# BatchE.net
KiCad netlist of a schematic drawn in EAGLE
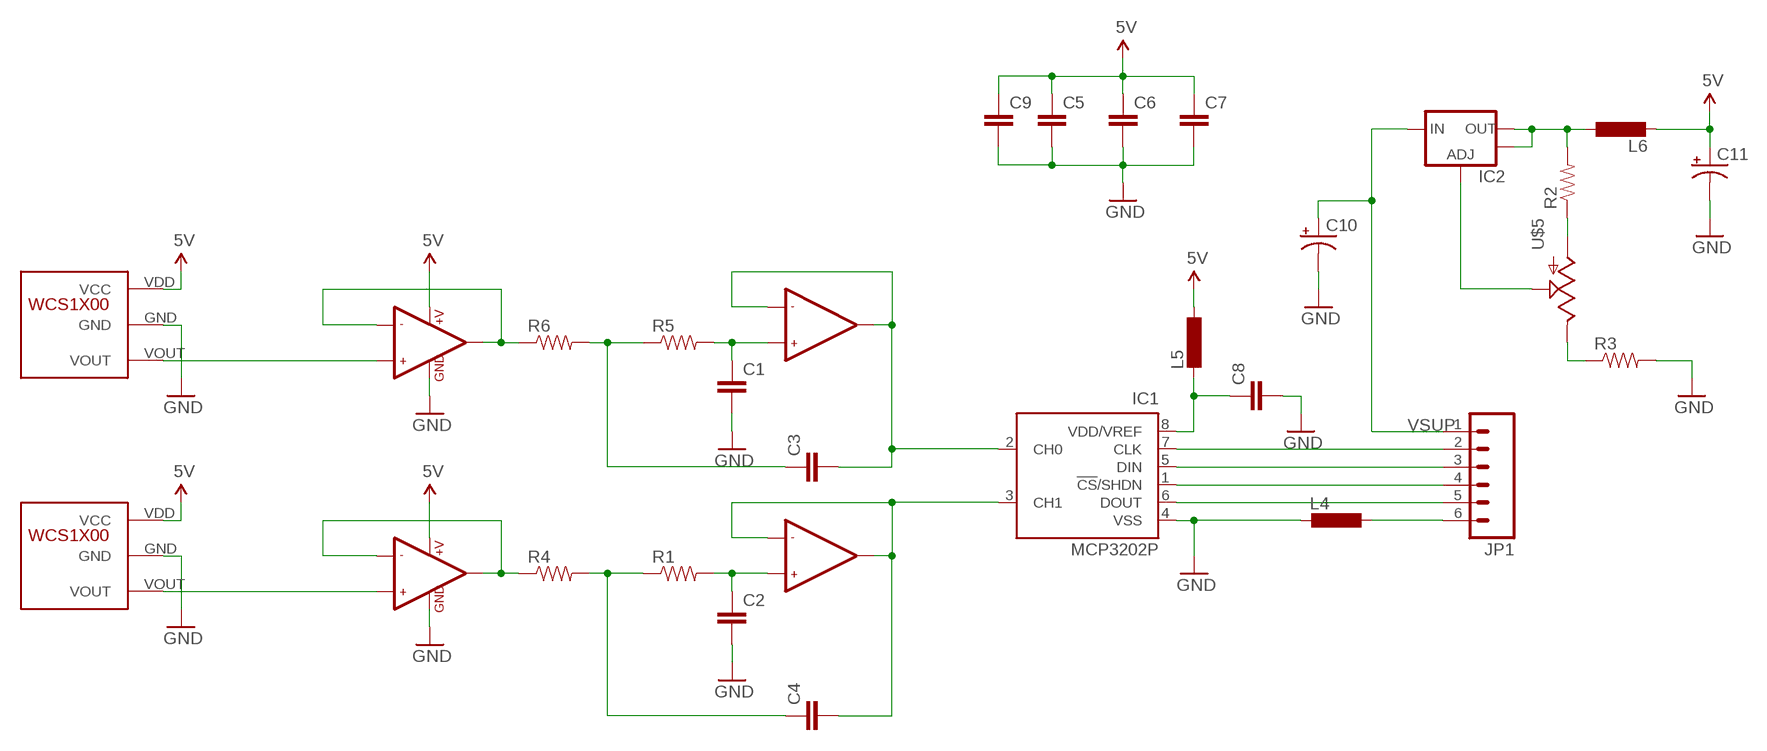
[diagram p0: schematic, sheet 1]
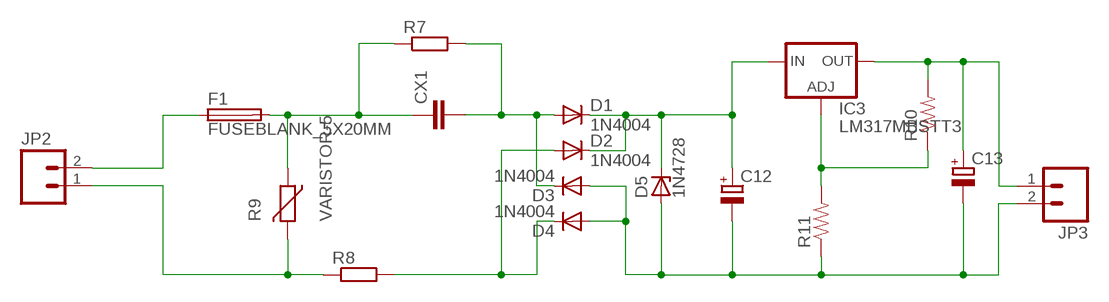
[diagram p1: schematic, sheet 2]
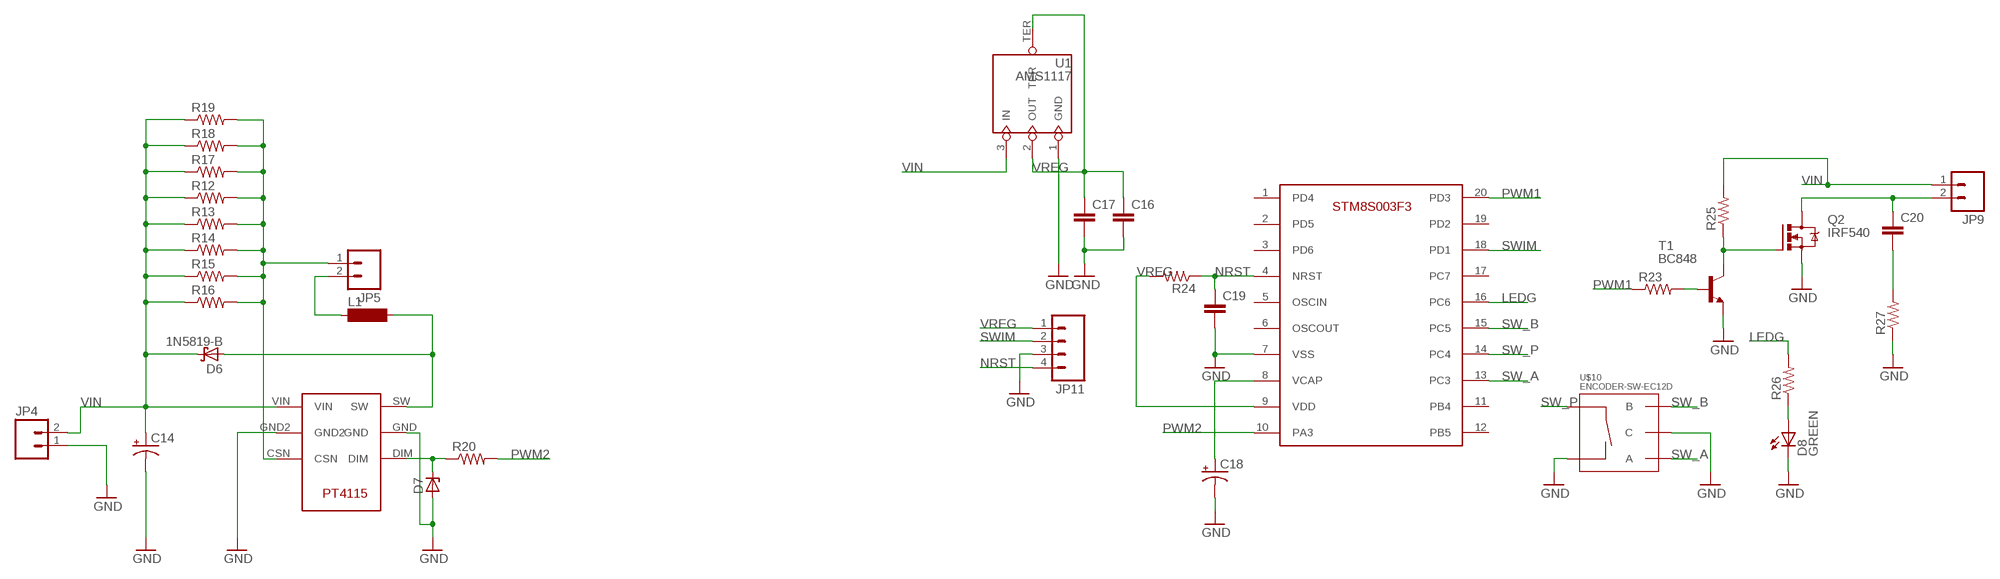
[diagram p2: schematic, sheet 3]

(export (version "E")
  (design (tool "Eeschema 10.0.6"))
  (components
    (comp (ref "C1")
      (value "CAP1206")
      (footprint "eagle-import:1206")
      (libsource (lib "eagle-import") (part "CAP1206"))
    )
    (comp (ref "C2")
      (value "CAP1206")
      (footprint "eagle-import:1206")
      (libsource (lib "eagle-import") (part "CAP1206"))
    )
    (comp (ref "C3")
      (value "CAP1206")
      (footprint "eagle-import:1206")
      (libsource (lib "eagle-import") (part "CAP1206"))
    )
    (comp (ref "C4")
      (value "CAP1206")
      (footprint "eagle-import:1206")
      (libsource (lib "eagle-import") (part "CAP1206"))
    )
    (comp (ref "C5")
      (value "CAP1206")
      (footprint "eagle-import:1206")
      (libsource (lib "eagle-import") (part "CAP1206"))
    )
    (comp (ref "C6")
      (value "CAP1206")
      (footprint "eagle-import:1206")
      (libsource (lib "eagle-import") (part "CAP1206"))
    )
    (comp (ref "C7")
      (value "CAP1206")
      (footprint "eagle-import:1206")
      (libsource (lib "eagle-import") (part "CAP1206"))
    )
    (comp (ref "C8")
      (value "CAP1206")
      (footprint "eagle-import:1206")
      (libsource (lib "eagle-import") (part "CAP1206"))
    )
    (comp (ref "C9")
      (value "CAP1206")
      (footprint "eagle-import:1206")
      (libsource (lib "eagle-import") (part "CAP1206"))
    )
    (comp (ref "C10")
      (value "CAP_POLPTH4")
      (footprint "eagle-import:CPOL-RADIAL-1000UF-25V")
      (libsource (lib "eagle-import") (part "CAP_POLPTH4"))
    )
    (comp (ref "C11")
      (value "CAP_POLPTH1")
      (footprint "eagle-import:CPOL-RADIAL-100UF-25V")
      (libsource (lib "eagle-import") (part "CAP_POLPTH1"))
    )
    (comp (ref "IC1")
      (value "MCP3202P")
      (footprint "eagle-import:DIL8")
      (fields (field (name "MF") "MICROCHIP") (field (name "MPN") "MCP3202-CI/P"))
      (libsource (lib "eagle-import") (part "MCP3202P"))
    )
    (comp (ref "IC2")
      (value "V_REG_LM1117SOT223")
      (footprint "eagle-import:SOT223")
      (libsource (lib "eagle-import") (part "V_REG_LM1117SOT223"))
    )
    (comp (ref "JP1")
      (value "M06LONGPADS")
      (footprint "eagle-import:1X06_LONGPADS")
      (libsource (lib "eagle-import") (part "M06LONGPADS"))
    )
    (comp (ref "L4")
      (value "L-EU0204V")
      (footprint "eagle-import:0204V")
      (libsource (lib "eagle-import") (part "L-EU0204V"))
    )
    (comp (ref "L5")
      (value "L-EU0204V")
      (footprint "eagle-import:0204V")
      (libsource (lib "eagle-import") (part "L-EU0204V"))
    )
    (comp (ref "L6")
      (value "L-EU0204V")
      (footprint "eagle-import:0204V")
      (libsource (lib "eagle-import") (part "L-EU0204V"))
    )
    (comp (ref "R1")
      (value "RESISTOR1206")
      (footprint "eagle-import:1206")
      (libsource (lib "eagle-import") (part "RESISTOR1206"))
    )
    (comp (ref "R2")
      (value "RESISTOR1206")
      (footprint "eagle-import:1206")
      (libsource (lib "eagle-import") (part "RESISTOR1206"))
    )
    (comp (ref "R3")
      (value "RESISTOR1206")
      (footprint "eagle-import:1206")
      (libsource (lib "eagle-import") (part "RESISTOR1206"))
    )
    (comp (ref "R4")
      (value "RESISTOR1206")
      (footprint "eagle-import:1206")
      (libsource (lib "eagle-import") (part "RESISTOR1206"))
    )
    (comp (ref "R5")
      (value "RESISTOR1206")
      (footprint "eagle-import:1206")
      (libsource (lib "eagle-import") (part "RESISTOR1206"))
    )
    (comp (ref "R6")
      (value "RESISTOR1206")
      (footprint "eagle-import:1206")
      (libsource (lib "eagle-import") (part "RESISTOR1206"))
    )
    (comp (ref "U$1")
      (value "LMV358")
      (footprint "eagle-import:SO08")
      (libsource (lib "eagle-import") (part "LMV358"))
    )
    (comp (ref "U$2")
      (value "LMV358")
      (footprint "eagle-import:SO08")
      (libsource (lib "eagle-import") (part "LMV358"))
    )
    (comp (ref "U$3")
      (value "WCS1X00")
      (footprint "eagle-import:WCS1X00")
      (libsource (lib "eagle-import") (part "WCS1X00"))
    )
    (comp (ref "U$4")
      (value "WCS1X00")
      (footprint "eagle-import:WCS1X00")
      (libsource (lib "eagle-import") (part "WCS1X00"))
    )
    (comp (ref "U$5")
      (value "POTTRIM")
      (footprint "eagle-import:TRIM_POT")
      (libsource (lib "eagle-import") (part "POTTRIM"))
    )
    (comp (ref "C12")
      (value "CPOL-EUE5-8.5")
      (footprint "eagle-import:E5-8,5")
      (libsource (lib "eagle-import") (part "CPOL-EUE5-8.5"))
    )
    (comp (ref "C13")
      (value "CPOL-EUE5-8.5")
      (footprint "eagle-import:E5-8,5")
      (libsource (lib "eagle-import") (part "CPOL-EUE5-8.5"))
    )
    (comp (ref "CX1")
      (value "CXXC15B8")
      (footprint "eagle-import:XC15B8")
      (libsource (lib "eagle-import") (part "CXXC15B8"))
    )
    (comp (ref "D1")
      (value "1N4004")
      (footprint "eagle-import:DO41-10")
      (libsource (lib "eagle-import") (part "1N4004"))
    )
    (comp (ref "D2")
      (value "1N4004")
      (footprint "eagle-import:DO41-10")
      (libsource (lib "eagle-import") (part "1N4004"))
    )
    (comp (ref "D3")
      (value "1N4004")
      (footprint "eagle-import:DO41-10")
      (libsource (lib "eagle-import") (part "1N4004"))
    )
    (comp (ref "D4")
      (value "1N4004")
      (footprint "eagle-import:DO41-10")
      (libsource (lib "eagle-import") (part "1N4004"))
    )
    (comp (ref "D5")
      (value "1N4728")
      (footprint "eagle-import:DO41Z10")
      (libsource (lib "eagle-import") (part "1N4728"))
    )
    (comp (ref "F1")
      (value "FUSEBLANK_5X20MM")
      (footprint "eagle-import:FUSE_HOLDER_5X20MM")
      (libsource (lib "eagle-import") (part "FUSEBLANK_5X20MM"))
    )
    (comp (ref "IC3")
      (value "LM317MBSTT3")
      (footprint "eagle-import:SOT223")
      (libsource (lib "eagle-import") (part "LM317?MBSTT3"))
    )
    (comp (ref "JP2")
      (value "M023.5MM")
      (footprint "eagle-import:SCREWTERMINAL-3.5MM-2")
      (libsource (lib "eagle-import") (part "M023.5MM"))
    )
    (comp (ref "JP3")
      (value "M023.5MM")
      (footprint "eagle-import:SCREWTERMINAL-3.5MM-2")
      (libsource (lib "eagle-import") (part "M023.5MM"))
    )
    (comp (ref "R7")
      (value "R-EU_0207/12")
      (footprint "eagle-import:0207_12")
      (libsource (lib "eagle-import") (part "R-EU_0207/12"))
    )
    (comp (ref "R8")
      (value "R-EU_0207/12")
      (footprint "eagle-import:0207_12")
      (libsource (lib "eagle-import") (part "R-EU_0207/12"))
    )
    (comp (ref "R9")
      (value "VARISTOR-5")
      (footprint "eagle-import:R-5")
      (libsource (lib "eagle-import") (part "VARISTOR-5"))
    )
    (comp (ref "R10")
      (value "RESISTOR0805-RES")
      (footprint "eagle-import:0805")
      (libsource (lib "eagle-import") (part "SparkFun-Resistors_RESISTOR0805-RES"))
    )
    (comp (ref "R11")
      (value "RESISTOR0805-RES")
      (footprint "eagle-import:0805")
      (libsource (lib "eagle-import") (part "SparkFun-Resistors_RESISTOR0805-RES"))
    )
    (comp (ref "C14")
      (value "CAP_POLPTH4")
      (footprint "eagle-import:CPOL-RADIAL-1000UF-25V")
      (libsource (lib "eagle-import") (part "CAP_POLPTH4"))
    )
    (comp (ref "C16")
      (value "CAP1206")
      (footprint "eagle-import:1206")
      (libsource (lib "eagle-import") (part "CAP1206"))
    )
    (comp (ref "C17")
      (value "CAP1206")
      (footprint "eagle-import:1206")
      (libsource (lib "eagle-import") (part "CAP1206"))
    )
    (comp (ref "C18")
      (value "CAP_POLPTH2")
      (footprint "eagle-import:CPOL-RADIAL-10UF-25V")
      (libsource (lib "eagle-import") (part "CAP_POLPTH2"))
    )
    (comp (ref "C19")
      (value "CAP1206")
      (footprint "eagle-import:1206")
      (libsource (lib "eagle-import") (part "CAP1206"))
    )
    (comp (ref "C20")
      (value "CAP1206")
      (footprint "eagle-import:1206")
      (libsource (lib "eagle-import") (part "CAP1206"))
    )
    (comp (ref "D6")
      (value "1N5819-B")
      (footprint "eagle-import:DO41-7.6")
      (libsource (lib "eagle-import") (part "1N5819-B"))
    )
    (comp (ref "D7")
      (value "ZENER-DIODEZD-7.5")
      (footprint "eagle-import:ZDIO-7.5")
      (libsource (lib "eagle-import") (part "ZENER-DIODEZD-7.5"))
    )
    (comp (ref "D8")
      (value "GREEN")
      (footprint "eagle-import:LED-1206")
      (libsource (lib "eagle-import") (part "LED-GREENLARGE"))
    )
    (comp (ref "JP4")
      (value "M02LOCK_LONGPADS")
      (footprint "eagle-import:1X02_LOCK_LONGPADS")
      (libsource (lib "eagle-import") (part "M02LOCK_LONGPADS"))
    )
    (comp (ref "JP5")
      (value "M02LOCK_LONGPADS")
      (footprint "eagle-import:1X02_LOCK_LONGPADS")
      (libsource (lib "eagle-import") (part "M02LOCK_LONGPADS"))
    )
    (comp (ref "JP9")
      (value "M02LOCK_LONGPADS")
      (footprint "eagle-import:1X02_LOCK_LONGPADS")
      (libsource (lib "eagle-import") (part "M02LOCK_LONGPADS"))
    )
    (comp (ref "JP11")
      (value "M04PTH")
      (footprint "eagle-import:1X04")
      (libsource (lib "eagle-import") (part "M04PTH"))
    )
    (comp (ref "L1")
      (value "BS11")
      (footprint "eagle-import:BS11")
      (libsource (lib "eagle-import") (part "BS11"))
    )
    (comp (ref "Q2")
      (value "IRF540")
      (footprint "eagle-import:TO220BV")
      (libsource (lib "eagle-import") (part "IRF540"))
    )
    (comp (ref "R12")
      (value "RESISTOR1206")
      (footprint "eagle-import:1206")
      (libsource (lib "eagle-import") (part "SparkFun-Resistors_RESISTOR1206"))
    )
    (comp (ref "R13")
      (value "RESISTOR1206")
      (footprint "eagle-import:1206")
      (libsource (lib "eagle-import") (part "SparkFun-Resistors_RESISTOR1206"))
    )
    (comp (ref "R14")
      (value "RESISTOR1206")
      (footprint "eagle-import:1206")
      (libsource (lib "eagle-import") (part "SparkFun-Resistors_RESISTOR1206"))
    )
    (comp (ref "R15")
      (value "RESISTOR1206")
      (footprint "eagle-import:1206")
      (libsource (lib "eagle-import") (part "SparkFun-Resistors_RESISTOR1206"))
    )
    (comp (ref "R16")
      (value "RESISTOR1206")
      (footprint "eagle-import:1206")
      (libsource (lib "eagle-import") (part "SparkFun-Resistors_RESISTOR1206"))
    )
    (comp (ref "R17")
      (value "RESISTOR1206")
      (footprint "eagle-import:1206")
      (libsource (lib "eagle-import") (part "SparkFun-Resistors_RESISTOR1206"))
    )
    (comp (ref "R18")
      (value "RESISTOR1206")
      (footprint "eagle-import:1206")
      (libsource (lib "eagle-import") (part "SparkFun-Resistors_RESISTOR1206"))
    )
    (comp (ref "R19")
      (value "RESISTOR1206")
      (footprint "eagle-import:1206")
      (libsource (lib "eagle-import") (part "SparkFun-Resistors_RESISTOR1206"))
    )
    (comp (ref "R20")
      (value "RESISTOR1206")
      (footprint "eagle-import:1206")
      (libsource (lib "eagle-import") (part "SparkFun-Resistors_RESISTOR1206"))
    )
    (comp (ref "R23")
      (value "RESISTOR0805-RES")
      (footprint "eagle-import:0805")
      (libsource (lib "eagle-import") (part "RESISTOR0805-RES"))
    )
    (comp (ref "R24")
      (value "RESISTOR0805-RES")
      (footprint "eagle-import:0805")
      (libsource (lib "eagle-import") (part "RESISTOR0805-RES"))
    )
    (comp (ref "R25")
      (value "RESISTOR0805-RES")
      (footprint "eagle-import:0805")
      (libsource (lib "eagle-import") (part "RESISTOR0805-RES"))
    )
    (comp (ref "R26")
      (value "RESISTOR0805-RES")
      (footprint "eagle-import:0805")
      (libsource (lib "eagle-import") (part "RESISTOR0805-RES"))
    )
    (comp (ref "R27")
      (value "RESISTOR0805-RES")
      (footprint "eagle-import:0805")
      (libsource (lib "eagle-import") (part "RESISTOR0805-RES"))
    )
    (comp (ref "T1")
      (value "BC848")
      (footprint "eagle-import:SOT23")
      (libsource (lib "eagle-import") (part "BC848"))
    )
    (comp (ref "U$6")
      (value "PT4115")
      (footprint "eagle-import:PT4115")
      (libsource (lib "eagle-import") (part "PT4115"))
    )
    (comp (ref "U$9")
      (value "STM8S003F3")
      (footprint "eagle-import:SSOP20")
      (libsource (lib "eagle-import") (part "STM8S003F3"))
    )
    (comp (ref "U$10")
      (value "ENCODER-SW-EC12D")
      (footprint "eagle-import:ENCODER-SW-EC12D")
      (libsource (lib "eagle-import") (part "ENCODER-SW-EC12D"))
    )
    (comp (ref "U1")
      (value "AMS1117")
      (footprint "eagle-import:SOT-223")
      (libsource (lib "eagle-import") (part "AMS1117"))
    )
  )
  (nets
    (net (code "1") (name "5V") (class "Default")
      (node (ref "C11") (pin "1") (pinfunction "+_1") (pintype "passive"))
      (node (ref "C5") (pin "1") (pinfunction "1_1") (pintype "passive"))
      (node (ref "C6") (pin "1") (pinfunction "1_1") (pintype "passive"))
      (node (ref "C7") (pin "1") (pinfunction "1_1") (pintype "passive"))
      (node (ref "C9") (pin "1") (pinfunction "1_1") (pintype "passive"))
      (node (ref "L5") (pin "1") (pinfunction "1_1") (pintype "passive"))
      (node (ref "L6") (pin "2") (pinfunction "2_2") (pintype "passive"))
      (node (ref "U$1") (pin "8") (pinfunction "+V_8") (pintype "power_in"))
      (node (ref "U$2") (pin "8") (pinfunction "+V_8") (pintype "power_in"))
      (node (ref "U$3") (pin "VDD") (pinfunction "VCC_VDD") (pintype "bidirectional"))
      (node (ref "U$4") (pin "VDD") (pinfunction "VCC_VDD") (pintype "bidirectional"))
    )
    (net (code "2") (name "GND") (class "Default")
      (node (ref "C1") (pin "2") (pinfunction "2_2") (pintype "passive"))
      (node (ref "C10") (pin "2") (pinfunction "-_2") (pintype "passive"))
      (node (ref "C11") (pin "2") (pinfunction "-_2") (pintype "passive"))
      (node (ref "C14") (pin "2") (pinfunction "-_2") (pintype "passive"))
      (node (ref "C16") (pin "2") (pinfunction "2_2") (pintype "passive"))
      (node (ref "C17") (pin "2") (pinfunction "2_2") (pintype "passive"))
      (node (ref "C18") (pin "2") (pinfunction "-_2") (pintype "passive"))
      (node (ref "C19") (pin "2") (pinfunction "2_2") (pintype "passive"))
      (node (ref "C2") (pin "2") (pinfunction "2_2") (pintype "passive"))
      (node (ref "C5") (pin "2") (pinfunction "2_2") (pintype "passive"))
      (node (ref "C6") (pin "2") (pinfunction "2_2") (pintype "passive"))
      (node (ref "C7") (pin "2") (pinfunction "2_2") (pintype "passive"))
      (node (ref "C8") (pin "2") (pinfunction "2_2") (pintype "passive"))
      (node (ref "C9") (pin "2") (pinfunction "2_2") (pintype "passive"))
      (node (ref "D7") (pin "A") (pinfunction "A_A") (pintype "passive"))
      (node (ref "D8") (pin "C") (pinfunction "C_C") (pintype "passive"))
      (node (ref "IC1") (pin "4") (pinfunction "VSS_4") (pintype "input"))
      (node (ref "JP11") (pin "3") (pinfunction "3_3") (pintype "passive"))
      (node (ref "JP4") (pin "1") (pinfunction "1_1") (pintype "passive"))
      (node (ref "L4") (pin "2") (pinfunction "2_2") (pintype "passive"))
      (node (ref "Q2") (pin "S") (pinfunction "S_S") (pintype "passive"))
      (node (ref "R27") (pin "1") (pinfunction "1_1") (pintype "passive"))
      (node (ref "R3") (pin "2") (pinfunction "2_2") (pintype "passive"))
      (node (ref "T1") (pin "2") (pinfunction "E_2") (pintype "passive"))
      (node (ref "U$1") (pin "4") (pinfunction "GND_4") (pintype "power_in"))
      (node (ref "U$10") (pin "4") (pinfunction "C_4") (pintype "bidirectional"))
      (node (ref "U$10") (pin "5") (pinfunction "SW-_5") (pintype "bidirectional"))
      (node (ref "U$2") (pin "4") (pinfunction "GND_4") (pintype "power_in"))
      (node (ref "U$3") (pin "GND") (pinfunction "GND_GND") (pintype "bidirectional"))
      (node (ref "U$4") (pin "GND") (pinfunction "GND_GND") (pintype "bidirectional"))
      (node (ref "U$6") (pin "GND") (pinfunction "GND_GND") (pintype "bidirectional"))
      (node (ref "U$6") (pin "GND2") (pinfunction "GND2_GND2") (pintype "bidirectional"))
      (node (ref "U$9") (pin "7") (pinfunction "VSS_7") (pintype "bidirectional"))
      (node (ref "U1") (pin "1") (pinfunction "GND_1") (pintype "bidirectional"))
    )
    (net (code "3") (name "LEDG") (class "Default")
      (node (ref "R26") (pin "2") (pinfunction "2_2") (pintype "passive"))
      (node (ref "U$9") (pin "16") (pinfunction "PC6_16") (pintype "bidirectional"))
    )
    (net (code "4") (name "NRST") (class "Default")
      (node (ref "C19") (pin "1") (pinfunction "1_1") (pintype "passive"))
      (node (ref "JP11") (pin "4") (pinfunction "4_4") (pintype "passive"))
      (node (ref "R24") (pin "1") (pinfunction "1_1") (pintype "passive"))
      (node (ref "U$9") (pin "4") (pinfunction "NRST_4") (pintype "bidirectional"))
    )
    (net (code "5") (name "Net-(C3-Pad1)") (class "Default")
      (node (ref "C3") (pin "1") (pinfunction "1_1") (pintype "passive"))
      (node (ref "R5") (pin "1") (pinfunction "1_1") (pintype "passive"))
      (node (ref "R6") (pin "2") (pinfunction "2_2") (pintype "passive"))
    )
    (net (code "6") (name "Net-(C4-Pad1)") (class "Default")
      (node (ref "C4") (pin "1") (pinfunction "1_1") (pintype "passive"))
      (node (ref "R1") (pin "1") (pinfunction "1_1") (pintype "passive"))
      (node (ref "R4") (pin "2") (pinfunction "2_2") (pintype "passive"))
    )
    (net (code "7") (name "Net-(C12-Pad-)") (class "Default")
      (node (ref "C12") (pin "-") (pinfunction "-_-") (pintype "passive"))
      (node (ref "C13") (pin "-") (pinfunction "-_-") (pintype "passive"))
      (node (ref "D3") (pin "A") (pinfunction "A_A") (pintype "passive"))
      (node (ref "D4") (pin "A") (pinfunction "A_A") (pintype "passive"))
      (node (ref "D5") (pin "A") (pinfunction "A_A") (pintype "passive"))
      (node (ref "JP3") (pin "2") (pinfunction "2_2") (pintype "passive"))
      (node (ref "R11") (pin "1") (pinfunction "1_1") (pintype "passive"))
    )
    (net (code "8") (name "Net-(C18-+)") (class "Default")
      (node (ref "C18") (pin "1") (pinfunction "+_1") (pintype "passive"))
      (node (ref "U$9") (pin "8") (pinfunction "VCAP_8") (pintype "bidirectional"))
    )
    (net (code "9") (name "Net-(C20-Pad1)") (class "Default")
      (node (ref "C20") (pin "1") (pinfunction "1_1") (pintype "passive"))
      (node (ref "JP9") (pin "2") (pinfunction "2_2") (pintype "passive"))
      (node (ref "Q2") (pin "D") (pinfunction "D_D") (pintype "passive"))
    )
    (net (code "10") (name "Net-(C20-Pad2)") (class "Default")
      (node (ref "C20") (pin "2") (pinfunction "2_2") (pintype "passive"))
      (node (ref "R27") (pin "2") (pinfunction "2_2") (pintype "passive"))
    )
    (net (code "11") (name "Net-(CX1-Pad1)") (class "Default")
      (node (ref "CX1") (pin "1") (pinfunction "1_1") (pintype "passive"))
      (node (ref "F1") (pin "2") (pinfunction "2_2") (pintype "passive"))
      (node (ref "R7") (pin "1") (pinfunction "1_1") (pintype "passive"))
      (node (ref "R9") (pin "1") (pinfunction "1_1") (pintype "passive"))
    )
    (net (code "12") (name "Net-(CX1-Pad2)") (class "Default")
      (node (ref "CX1") (pin "2") (pinfunction "2_2") (pintype "passive"))
      (node (ref "D1") (pin "A") (pinfunction "A_A") (pintype "passive"))
      (node (ref "D3") (pin "C") (pinfunction "C_C") (pintype "passive"))
      (node (ref "R7") (pin "2") (pinfunction "2_2") (pintype "passive"))
    )
    (net (code "13") (name "Net-(D2-PadA)") (class "Default")
      (node (ref "D2") (pin "A") (pinfunction "A_A") (pintype "passive"))
      (node (ref "D4") (pin "C") (pinfunction "C_C") (pintype "passive"))
      (node (ref "R8") (pin "2") (pinfunction "2_2") (pintype "passive"))
    )
    (net (code "14") (name "Net-(D6-PadA)") (class "Default")
      (node (ref "D6") (pin "A") (pinfunction "A_A") (pintype "passive"))
      (node (ref "L1") (pin "2") (pinfunction "2_2") (pintype "passive"))
      (node (ref "U$6") (pin "SW") (pinfunction "SW_SW") (pintype "bidirectional"))
    )
    (net (code "15") (name "Net-(D7-PadC)") (class "Default")
      (node (ref "D7") (pin "C") (pinfunction "C_C") (pintype "passive"))
      (node (ref "R20") (pin "1") (pinfunction "1_1") (pintype "passive"))
      (node (ref "U$6") (pin "DIM") (pinfunction "DIM_DIM") (pintype "bidirectional"))
    )
    (net (code "16") (name "Net-(D8-PadA)") (class "Default")
      (node (ref "D8") (pin "A") (pinfunction "A_A") (pintype "passive"))
      (node (ref "R26") (pin "1") (pinfunction "1_1") (pintype "passive"))
    )
    (net (code "17") (name "Net-(F1-Pad1)") (class "Default")
      (node (ref "F1") (pin "1") (pinfunction "1_1") (pintype "passive"))
      (node (ref "JP2") (pin "2") (pinfunction "2_2") (pintype "passive"))
    )
    (net (code "18") (name "Net-(IC1-CH0)") (class "Default")
      (node (ref "C3") (pin "2") (pinfunction "2_2") (pintype "passive"))
      (node (ref "IC1") (pin "2") (pinfunction "CH0_2") (pintype "input"))
      (node (ref "U$1") (pin "6") (pinfunction "-IN2_6") (pintype "input"))
      (node (ref "U$1") (pin "7") (pinfunction "OUT2_7") (pintype "output"))
    )
    (net (code "19") (name "Net-(IC1-CH1)") (class "Default")
      (node (ref "C4") (pin "2") (pinfunction "2_2") (pintype "passive"))
      (node (ref "IC1") (pin "3") (pinfunction "CH1_3") (pintype "input"))
      (node (ref "U$2") (pin "6") (pinfunction "-IN2_6") (pintype "input"))
      (node (ref "U$2") (pin "7") (pinfunction "OUT2_7") (pintype "output"))
    )
    (net (code "20") (name "Net-(IC1-CLK)") (class "Default")
      (node (ref "IC1") (pin "7") (pinfunction "CLK_7") (pintype "input"))
      (node (ref "JP1") (pin "2") (pinfunction "2_2") (pintype "passive"))
    )
    (net (code "21") (name "Net-(IC1-DIN)") (class "Default")
      (node (ref "IC1") (pin "5") (pinfunction "DIN_5") (pintype "input"))
      (node (ref "JP1") (pin "3") (pinfunction "3_3") (pintype "passive"))
    )
    (net (code "22") (name "Net-(IC1-DOUT)") (class "Default")
      (node (ref "IC1") (pin "6") (pinfunction "DOUT_6") (pintype "input"))
      (node (ref "JP1") (pin "5") (pinfunction "5_5") (pintype "passive"))
    )
    (net (code "23") (name "Net-(IC1-VDD{slash}VREF)") (class "Default")
      (node (ref "C8") (pin "1") (pinfunction "1_1") (pintype "passive"))
      (node (ref "IC1") (pin "8") (pinfunction "VDD/VREF_8") (pintype "input"))
      (node (ref "L5") (pin "2") (pinfunction "2_2") (pintype "passive"))
    )
    (net (code "24") (name "Net-(IC1-~{CS}{slash}SHDN)") (class "Default")
      (node (ref "IC1") (pin "1") (pinfunction "~{CS}/SHDN_1") (pintype "input"))
      (node (ref "JP1") (pin "4") (pinfunction "4_4") (pintype "passive"))
    )
    (net (code "25") (name "Net-(IC2-ADJ)") (class "Default")
      (node (ref "IC2") (pin "1") (pinfunction "ADJ_1") (pintype "input"))
      (node (ref "U$5") (pin "1") (pinfunction "S_1") (pintype "passive"))
    )
    (net (code "26") (name "Net-(IC2-OUT-Pad2)") (class "Default")
      (node (ref "IC2") (pin "2") (pinfunction "OUT_2") (pintype "output"))
      (node (ref "IC2") (pin "4") (pinfunction "OUT_4") (pintype "output"))
      (node (ref "L6") (pin "1") (pinfunction "1_1") (pintype "passive"))
      (node (ref "R2") (pin "2") (pinfunction "2_2") (pintype "passive"))
    )
    (net (code "27") (name "Net-(IC3-ADJ)") (class "Default")
      (node (ref "IC3") (pin "1") (pinfunction "ADJ_1") (pintype "input"))
      (node (ref "R10") (pin "1") (pinfunction "1_1") (pintype "passive"))
      (node (ref "R11") (pin "2") (pinfunction "2_2") (pintype "passive"))
    )
    (net (code "28") (name "Net-(IC3-IN)") (class "Default")
      (node (ref "C12") (pin "+") (pinfunction "+_+") (pintype "passive"))
      (node (ref "D1") (pin "C") (pinfunction "C_C") (pintype "passive"))
      (node (ref "D2") (pin "C") (pinfunction "C_C") (pintype "passive"))
      (node (ref "D5") (pin "C") (pinfunction "C_C") (pintype "passive"))
      (node (ref "IC3") (pin "3") (pinfunction "IN_3") (pintype "input"))
    )
    (net (code "29") (name "Net-(IC3-OUT)") (class "Default")
      (node (ref "C13") (pin "+") (pinfunction "+_+") (pintype "passive"))
      (node (ref "IC3") (pin "4") (pinfunction "OUT_4") (pintype "passive"))
      (node (ref "JP3") (pin "1") (pinfunction "1_1") (pintype "passive"))
      (node (ref "R10") (pin "2") (pinfunction "2_2") (pintype "passive"))
    )
    (net (code "30") (name "Net-(JP1-Pad6)") (class "Default")
      (node (ref "JP1") (pin "6") (pinfunction "6_6") (pintype "passive"))
      (node (ref "L4") (pin "1") (pinfunction "1_1") (pintype "passive"))
    )
    (net (code "31") (name "Net-(JP2-Pad1)") (class "Default")
      (node (ref "JP2") (pin "1") (pinfunction "1_1") (pintype "passive"))
      (node (ref "R8") (pin "1") (pinfunction "1_1") (pintype "passive"))
      (node (ref "R9") (pin "2") (pinfunction "2_2") (pintype "passive"))
    )
    (net (code "32") (name "Net-(JP5-Pad1)") (class "Default")
      (node (ref "JP5") (pin "1") (pinfunction "1_1") (pintype "passive"))
      (node (ref "R12") (pin "2") (pinfunction "2_2") (pintype "passive"))
      (node (ref "R13") (pin "2") (pinfunction "2_2") (pintype "passive"))
      (node (ref "R14") (pin "2") (pinfunction "2_2") (pintype "passive"))
      (node (ref "R15") (pin "2") (pinfunction "2_2") (pintype "passive"))
      (node (ref "R16") (pin "2") (pinfunction "2_2") (pintype "passive"))
      (node (ref "R17") (pin "2") (pinfunction "2_2") (pintype "passive"))
      (node (ref "R18") (pin "2") (pinfunction "2_2") (pintype "passive"))
      (node (ref "R19") (pin "2") (pinfunction "2_2") (pintype "passive"))
      (node (ref "U$6") (pin "CSN") (pinfunction "CSN_CSN") (pintype "bidirectional"))
    )
    (net (code "33") (name "Net-(JP5-Pad2)") (class "Default")
      (node (ref "JP5") (pin "2") (pinfunction "2_2") (pintype "passive"))
      (node (ref "L1") (pin "1") (pinfunction "1_1") (pintype "passive"))
    )
    (net (code "34") (name "Net-(T1-B)") (class "Default")
      (node (ref "R23") (pin "2") (pinfunction "2_2") (pintype "passive"))
      (node (ref "T1") (pin "1") (pinfunction "B_1") (pintype "passive"))
    )
    (net (code "35") (name "Net-(T1-C)") (class "Default")
      (node (ref "Q2") (pin "G") (pinfunction "G_G") (pintype "passive"))
      (node (ref "R25") (pin "1") (pinfunction "1_1") (pintype "passive"))
      (node (ref "T1") (pin "3") (pinfunction "C_3") (pintype "passive"))
    )
    (net (code "36") (name "Net-(U$1A-+IN1)") (class "Default")
      (node (ref "U$1") (pin "3") (pinfunction "+IN1_3") (pintype "input"))
      (node (ref "U$3") (pin "VOUT") (pinfunction "VOUT_VOUT") (pintype "bidirectional"))
    )
    (net (code "37") (name "Net-(U$1A--IN1)") (class "Default")
      (node (ref "R6") (pin "1") (pinfunction "1_1") (pintype "passive"))
      (node (ref "U$1") (pin "1") (pinfunction "OUT1_1") (pintype "output"))
      (node (ref "U$1") (pin "2") (pinfunction "-IN1_2") (pintype "input"))
    )
    (net (code "38") (name "Net-(U$1B-+IN2)") (class "Default")
      (node (ref "C1") (pin "1") (pinfunction "1_1") (pintype "passive"))
      (node (ref "R5") (pin "2") (pinfunction "2_2") (pintype "passive"))
      (node (ref "U$1") (pin "5") (pinfunction "+IN2_5") (pintype "input"))
    )
    (net (code "39") (name "Net-(U$2A-+IN1)") (class "Default")
      (node (ref "U$2") (pin "3") (pinfunction "+IN1_3") (pintype "input"))
      (node (ref "U$4") (pin "VOUT") (pinfunction "VOUT_VOUT") (pintype "bidirectional"))
    )
    (net (code "40") (name "Net-(U$2A--IN1)") (class "Default")
      (node (ref "R4") (pin "1") (pinfunction "1_1") (pintype "passive"))
      (node (ref "U$2") (pin "1") (pinfunction "OUT1_1") (pintype "output"))
      (node (ref "U$2") (pin "2") (pinfunction "-IN1_2") (pintype "input"))
    )
    (net (code "41") (name "Net-(U$2B-+IN2)") (class "Default")
      (node (ref "C2") (pin "1") (pinfunction "1_1") (pintype "passive"))
      (node (ref "R1") (pin "2") (pinfunction "2_2") (pintype "passive"))
      (node (ref "U$2") (pin "5") (pinfunction "+IN2_5") (pintype "input"))
    )
    (net (code "42") (name "Net-(U$5-A)") (class "Default")
      (node (ref "R2") (pin "1") (pinfunction "1_1") (pintype "passive"))
      (node (ref "U$5") (pin "3") (pinfunction "A_3") (pintype "passive"))
    )
    (net (code "43") (name "Net-(U$5-E)") (class "Default")
      (node (ref "R3") (pin "1") (pinfunction "1_1") (pintype "passive"))
      (node (ref "U$5") (pin "2") (pinfunction "E_2") (pintype "passive"))
    )
    (net (code "44") (name "PWM1") (class "Default")
      (node (ref "R23") (pin "1") (pinfunction "1_1") (pintype "passive"))
      (node (ref "U$9") (pin "20") (pinfunction "PD3_20") (pintype "bidirectional"))
    )
    (net (code "45") (name "PWM2") (class "Default")
      (node (ref "R20") (pin "2") (pinfunction "2_2") (pintype "passive"))
      (node (ref "U$9") (pin "10") (pinfunction "PA3_10") (pintype "bidirectional"))
    )
    (net (code "46") (name "SWIM") (class "Default")
      (node (ref "JP11") (pin "2") (pinfunction "2_2") (pintype "passive"))
      (node (ref "U$9") (pin "18") (pinfunction "PD1_18") (pintype "bidirectional"))
    )
    (net (code "47") (name "SW_A") (class "Default")
      (node (ref "U$10") (pin "1") (pinfunction "A_1") (pintype "bidirectional"))
      (node (ref "U$9") (pin "13") (pinfunction "PC3_13") (pintype "bidirectional"))
    )
    (net (code "48") (name "SW_B") (class "Default")
      (node (ref "U$10") (pin "3") (pinfunction "B_3") (pintype "bidirectional"))
      (node (ref "U$9") (pin "15") (pinfunction "PC5_15") (pintype "bidirectional"))
    )
    (net (code "49") (name "SW_P") (class "Default")
      (node (ref "U$10") (pin "2") (pinfunction "SW+_2") (pintype "bidirectional"))
      (node (ref "U$9") (pin "14") (pinfunction "PC4_14") (pintype "bidirectional"))
    )
    (net (code "50") (name "VIN") (class "Default")
      (node (ref "C14") (pin "1") (pinfunction "+_1") (pintype "passive"))
      (node (ref "D6") (pin "C") (pinfunction "C_C") (pintype "passive"))
      (node (ref "JP4") (pin "2") (pinfunction "2_2") (pintype "passive"))
      (node (ref "JP9") (pin "1") (pinfunction "1_1") (pintype "passive"))
      (node (ref "R12") (pin "1") (pinfunction "1_1") (pintype "passive"))
      (node (ref "R13") (pin "1") (pinfunction "1_1") (pintype "passive"))
      (node (ref "R14") (pin "1") (pinfunction "1_1") (pintype "passive"))
      (node (ref "R15") (pin "1") (pinfunction "1_1") (pintype "passive"))
      (node (ref "R16") (pin "1") (pinfunction "1_1") (pintype "passive"))
      (node (ref "R17") (pin "1") (pinfunction "1_1") (pintype "passive"))
      (node (ref "R18") (pin "1") (pinfunction "1_1") (pintype "passive"))
      (node (ref "R19") (pin "1") (pinfunction "1_1") (pintype "passive"))
      (node (ref "R25") (pin "2") (pinfunction "2_2") (pintype "passive"))
      (node (ref "U$6") (pin "VIN") (pinfunction "VIN_VIN") (pintype "bidirectional"))
      (node (ref "U1") (pin "3") (pinfunction "IN_3") (pintype "bidirectional"))
    )
    (net (code "51") (name "VREG") (class "Default")
      (node (ref "C16") (pin "1") (pinfunction "1_1") (pintype "passive"))
      (node (ref "C17") (pin "1") (pinfunction "1_1") (pintype "passive"))
      (node (ref "JP11") (pin "1") (pinfunction "1_1") (pintype "passive"))
      (node (ref "R24") (pin "2") (pinfunction "2_2") (pintype "passive"))
      (node (ref "U$9") (pin "9") (pinfunction "VDD_9") (pintype "bidirectional"))
      (node (ref "U1") (pin "2") (pinfunction "OUT_2") (pintype "bidirectional"))
      (node (ref "U1") (pin "TER") (pinfunction "TER_TER") (pintype "bidirectional"))
    )
    (net (code "52") (name "VSUP") (class "Default")
      (node (ref "C10") (pin "1") (pinfunction "+_1") (pintype "passive"))
      (node (ref "IC2") (pin "3") (pinfunction "IN_3") (pintype "input"))
      (node (ref "JP1") (pin "1") (pinfunction "1_1") (pintype "passive"))
    )
    (net (code "53") (name "unconnected-(U$9-OSCIN-Pad5)") (class "Default")
      (node (ref "U$9") (pin "5") (pinfunction "OSCIN_5") (pintype "bidirectional"))
    )
    (net (code "54") (name "unconnected-(U$9-OSCOUT-Pad6)") (class "Default")
      (node (ref "U$9") (pin "6") (pinfunction "OSCOUT_6") (pintype "bidirectional"))
    )
    (net (code "55") (name "unconnected-(U$9-PB4-Pad11)") (class "Default")
      (node (ref "U$9") (pin "11") (pinfunction "PB4_11") (pintype "bidirectional"))
    )
    (net (code "56") (name "unconnected-(U$9-PB5-Pad12)") (class "Default")
      (node (ref "U$9") (pin "12") (pinfunction "PB5_12") (pintype "bidirectional"))
    )
    (net (code "57") (name "unconnected-(U$9-PC7-Pad17)") (class "Default")
      (node (ref "U$9") (pin "17") (pinfunction "PC7_17") (pintype "bidirectional"))
    )
    (net (code "58") (name "unconnected-(U$9-PD2-Pad19)") (class "Default")
      (node (ref "U$9") (pin "19") (pinfunction "PD2_19") (pintype "bidirectional"))
    )
    (net (code "59") (name "unconnected-(U$9-PD4-Pad1)") (class "Default")
      (node (ref "U$9") (pin "1") (pinfunction "PD4_1") (pintype "bidirectional"))
    )
    (net (code "60") (name "unconnected-(U$9-PD5-Pad2)") (class "Default")
      (node (ref "U$9") (pin "2") (pinfunction "PD5_2") (pintype "bidirectional"))
    )
    (net (code "61") (name "unconnected-(U$9-PD6-Pad3)") (class "Default")
      (node (ref "U$9") (pin "3") (pinfunction "PD6_3") (pintype "bidirectional"))
    )
  )
)
